# cartemoteur.net
KiCad netlist of a schematic drawn in EAGLE
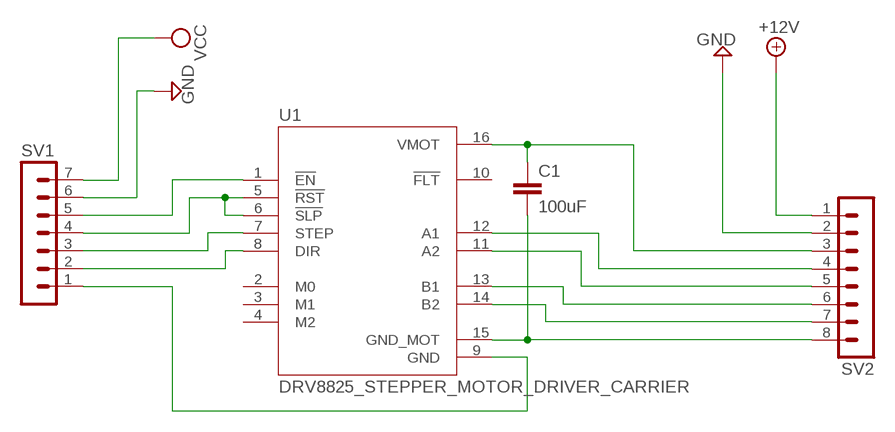
[diagram p0: schematic, sheet 1]

(export (version "E")
  (design (tool "Eeschema 10.0.6"))
  (components
    (comp (ref "C1")
      (value "100uF")
      (footprint "eagle-import:C025-024X044")
      (libsource (lib "eagle-import") (part "C-EU025-024X044"))
    )
    (comp (ref "SV1")
      (value "MA07-1")
      (footprint "eagle-import:MA07-1")
      (libsource (lib "eagle-import") (part "MA07-1"))
    )
    (comp (ref "SV2")
      (value "MA08-1")
      (footprint "eagle-import:MA08-1")
      (libsource (lib "eagle-import") (part "MA08-1"))
    )
    (comp (ref "U1")
      (value "DRV8825_STEPPER_MOTOR_DRIVER_CARRIER")
      (footprint "eagle-import:IC_DRV8825_STEPPER_MOTOR_DRIVER_CARRIER")
      (fields (field (name "MF") "Pololu") (field (name "MP") "DRV8825 STEPPER MOTOR DRIVER CARRIER"))
      (libsource (lib "eagle-import") (part "DRV8825_STEPPER_MOTOR_DRIVER_CARRIER"))
    )
  )
  (nets
    (net (code "1") (name "+12V") (class "Default")
      (node (ref "SV2") (pin "1") (pinfunction "1_1") (pintype "passive"))
    )
    (net (code "2") (name "GND") (class "Default")
      (node (ref "SV1") (pin "6") (pinfunction "6_6") (pintype "passive"))
      (node (ref "SV2") (pin "2") (pinfunction "2_2") (pintype "passive"))
    )
    (net (code "3") (name "Net-(U1-A1)") (class "Default")
      (node (ref "SV2") (pin "4") (pinfunction "4_4") (pintype "passive"))
      (node (ref "U1") (pin "12") (pinfunction "A1_12") (pintype "output"))
    )
    (net (code "4") (name "Net-(U1-A2)") (class "Default")
      (node (ref "SV2") (pin "5") (pinfunction "5_5") (pintype "passive"))
      (node (ref "U1") (pin "11") (pinfunction "A2_11") (pintype "output"))
    )
    (net (code "5") (name "Net-(U1-B1)") (class "Default")
      (node (ref "SV2") (pin "6") (pinfunction "6_6") (pintype "passive"))
      (node (ref "U1") (pin "13") (pinfunction "B1_13") (pintype "output"))
    )
    (net (code "6") (name "Net-(U1-B2)") (class "Default")
      (node (ref "SV2") (pin "7") (pinfunction "7_7") (pintype "passive"))
      (node (ref "U1") (pin "14") (pinfunction "B2_14") (pintype "output"))
    )
    (net (code "7") (name "Net-(U1-DIR)") (class "Default")
      (node (ref "SV1") (pin "2") (pinfunction "2_2") (pintype "passive"))
      (node (ref "U1") (pin "8") (pinfunction "DIR_8") (pintype "input"))
    )
    (net (code "8") (name "Net-(U1-GND)") (class "Default")
      (node (ref "SV1") (pin "1") (pinfunction "1_1") (pintype "passive"))
      (node (ref "U1") (pin "9") (pinfunction "GND_9") (pintype "power_in"))
    )
    (net (code "9") (name "Net-(U1-GND_MOT)") (class "Default")
      (node (ref "C1") (pin "2") (pinfunction "2_2") (pintype "passive"))
      (node (ref "SV2") (pin "8") (pinfunction "8_8") (pintype "passive"))
      (node (ref "U1") (pin "15") (pinfunction "GND_MOT_15") (pintype "power_in"))
    )
    (net (code "10") (name "Net-(U1-STEP)") (class "Default")
      (node (ref "SV1") (pin "3") (pinfunction "3_3") (pintype "passive"))
      (node (ref "U1") (pin "7") (pinfunction "STEP_7") (pintype "input"))
    )
    (net (code "11") (name "Net-(U1-VMOT)") (class "Default")
      (node (ref "C1") (pin "1") (pinfunction "1_1") (pintype "passive"))
      (node (ref "SV2") (pin "3") (pinfunction "3_3") (pintype "passive"))
      (node (ref "U1") (pin "16") (pinfunction "VMOT_16") (pintype "power_in"))
    )
    (net (code "12") (name "Net-(U1-~{EN})") (class "Default")
      (node (ref "SV1") (pin "5") (pinfunction "5_5") (pintype "passive"))
      (node (ref "U1") (pin "1") (pinfunction "~{EN}_1") (pintype "input"))
    )
    (net (code "13") (name "Net-(U1-~{RST})") (class "Default")
      (node (ref "SV1") (pin "4") (pinfunction "4_4") (pintype "passive"))
      (node (ref "U1") (pin "5") (pinfunction "~{RST}_5") (pintype "input"))
      (node (ref "U1") (pin "6") (pinfunction "~{SLP}_6") (pintype "input"))
    )
    (net (code "14") (name "VCC") (class "Default")
      (node (ref "SV1") (pin "7") (pinfunction "7_7") (pintype "passive"))
    )
    (net (code "15") (name "unconnected-(U1-M0-Pad2)") (class "Default")
      (node (ref "U1") (pin "2") (pinfunction "M0_2") (pintype "input"))
    )
    (net (code "16") (name "unconnected-(U1-M1-Pad3)") (class "Default")
      (node (ref "U1") (pin "3") (pinfunction "M1_3") (pintype "input"))
    )
    (net (code "17") (name "unconnected-(U1-M2-Pad4)") (class "Default")
      (node (ref "U1") (pin "4") (pinfunction "M2_4") (pintype "input"))
    )
    (net (code "18") (name "unconnected-(U1-~{FLT}-Pad10)") (class "Default")
      (node (ref "U1") (pin "10") (pinfunction "~{FLT}_10") (pintype "output"))
    )
  )
)
